# Soccer_V4.net
KiCad netlist of a schematic drawn in EAGLE
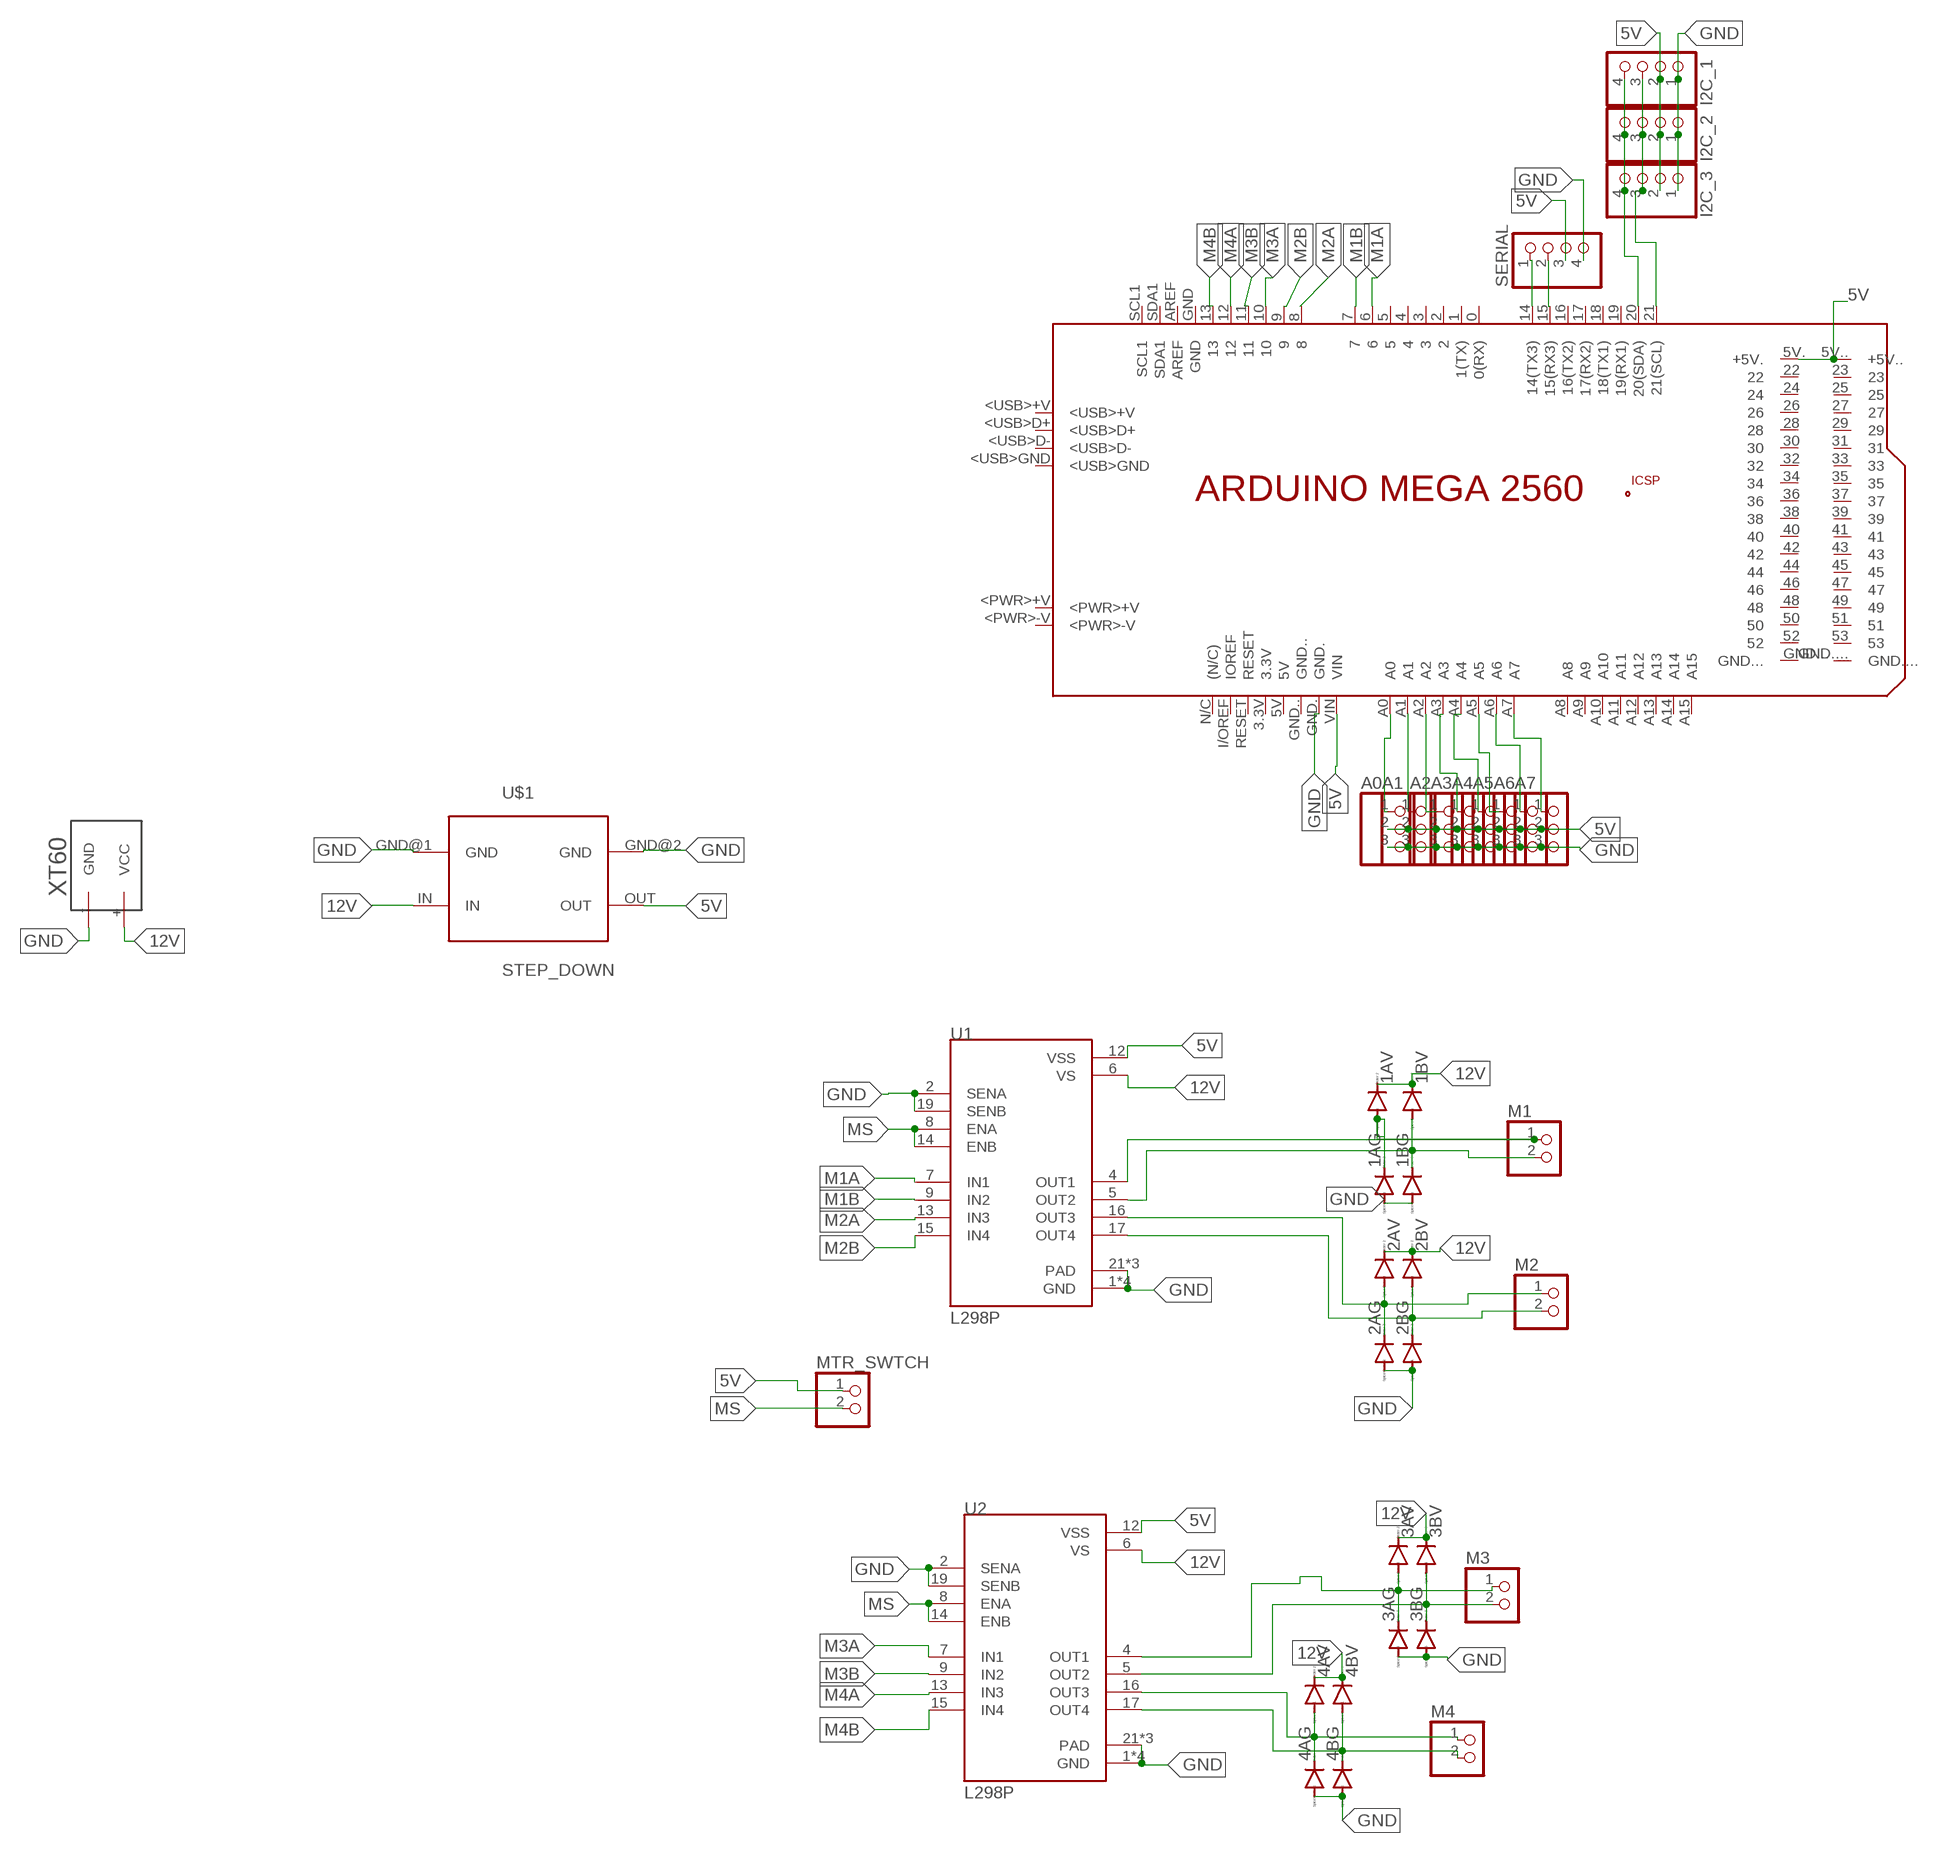
[diagram p0: schematic, sheet 1]

(export (version "E")
  (design (tool "Eeschema 10.0.6"))
  (components
    (comp (ref "1AG")
      (value "1N4004")
      (footprint "eagle-import:DO41-10")
      (libsource (lib "eagle-import") (part "1N4004"))
    )
    (comp (ref "1AV")
      (value "1N4004")
      (footprint "eagle-import:DO41-10")
      (libsource (lib "eagle-import") (part "1N4004"))
    )
    (comp (ref "1BG")
      (value "1N4004")
      (footprint "eagle-import:DO41-10")
      (libsource (lib "eagle-import") (part "1N4004"))
    )
    (comp (ref "1BV")
      (value "1N4004")
      (footprint "eagle-import:DO41-10")
      (libsource (lib "eagle-import") (part "1N4004"))
    )
    (comp (ref "2AG")
      (value "1N4004")
      (footprint "eagle-import:DO41-10")
      (libsource (lib "eagle-import") (part "1N4004"))
    )
    (comp (ref "2AV")
      (value "1N4004")
      (footprint "eagle-import:DO41-10")
      (libsource (lib "eagle-import") (part "1N4004"))
    )
    (comp (ref "2BG")
      (value "1N4004")
      (footprint "eagle-import:DO41-10")
      (libsource (lib "eagle-import") (part "1N4004"))
    )
    (comp (ref "2BV")
      (value "1N4004")
      (footprint "eagle-import:DO41-10")
      (libsource (lib "eagle-import") (part "1N4004"))
    )
    (comp (ref "3AG")
      (value "1N4004")
      (footprint "eagle-import:DO41-10")
      (libsource (lib "eagle-import") (part "1N4004"))
    )
    (comp (ref "3AV")
      (value "1N4004")
      (footprint "eagle-import:DO41-10")
      (libsource (lib "eagle-import") (part "1N4004"))
    )
    (comp (ref "3BG")
      (value "1N4004")
      (footprint "eagle-import:DO41-10")
      (libsource (lib "eagle-import") (part "1N4004"))
    )
    (comp (ref "3BV")
      (value "1N4004")
      (footprint "eagle-import:DO41-10")
      (libsource (lib "eagle-import") (part "1N4004"))
    )
    (comp (ref "4AG")
      (value "1N4004")
      (footprint "eagle-import:DO41-10")
      (libsource (lib "eagle-import") (part "1N4004"))
    )
    (comp (ref "4AV")
      (value "1N4004")
      (footprint "eagle-import:DO41-10")
      (libsource (lib "eagle-import") (part "1N4004"))
    )
    (comp (ref "4BG")
      (value "1N4004")
      (footprint "eagle-import:DO41-10")
      (libsource (lib "eagle-import") (part "1N4004"))
    )
    (comp (ref "4BV")
      (value "1N4004")
      (footprint "eagle-import:DO41-10")
      (libsource (lib "eagle-import") (part "1N4004"))
    )
    (comp (ref "A0")
      (value "PINHD-1X3")
      (footprint "eagle-import:1X03")
      (libsource (lib "eagle-import") (part "PINHD-1X3"))
    )
    (comp (ref "A1")
      (value "PINHD-1X3")
      (footprint "eagle-import:1X03")
      (libsource (lib "eagle-import") (part "PINHD-1X3"))
    )
    (comp (ref "A2")
      (value "PINHD-1X3")
      (footprint "eagle-import:1X03")
      (libsource (lib "eagle-import") (part "PINHD-1X3"))
    )
    (comp (ref "A3")
      (value "PINHD-1X3")
      (footprint "eagle-import:1X03")
      (libsource (lib "eagle-import") (part "PINHD-1X3"))
    )
    (comp (ref "A4")
      (value "PINHD-1X3")
      (footprint "eagle-import:1X03")
      (libsource (lib "eagle-import") (part "PINHD-1X3"))
    )
    (comp (ref "A5")
      (value "PINHD-1X3")
      (footprint "eagle-import:1X03")
      (libsource (lib "eagle-import") (part "PINHD-1X3"))
    )
    (comp (ref "A6")
      (value "PINHD-1X3")
      (footprint "eagle-import:1X03")
      (libsource (lib "eagle-import") (part "PINHD-1X3"))
    )
    (comp (ref "A7")
      (value "PINHD-1X3")
      (footprint "eagle-import:1X03")
      (libsource (lib "eagle-import") (part "PINHD-1X3"))
    )
    (comp (ref "I2C_1")
      (value "PINHD-1X4")
      (footprint "eagle-import:1X04")
      (libsource (lib "eagle-import") (part "PINHD-1X4"))
    )
    (comp (ref "I2C_2")
      (value "PINHD-1X4")
      (footprint "eagle-import:1X04")
      (libsource (lib "eagle-import") (part "PINHD-1X4"))
    )
    (comp (ref "I2C_3")
      (value "PINHD-1X4")
      (footprint "eagle-import:1X04")
      (libsource (lib "eagle-import") (part "PINHD-1X4"))
    )
    (comp (ref "M1")
      (value "PINHD-1X2")
      (footprint "eagle-import:1X02")
      (libsource (lib "eagle-import") (part "PINHD-1X2"))
    )
    (comp (ref "M2")
      (value "PINHD-1X2")
      (footprint "eagle-import:1X02")
      (libsource (lib "eagle-import") (part "PINHD-1X2"))
    )
    (comp (ref "M3")
      (value "PINHD-1X2")
      (footprint "eagle-import:1X02")
      (libsource (lib "eagle-import") (part "PINHD-1X2"))
    )
    (comp (ref "M4")
      (value "PINHD-1X2")
      (footprint "eagle-import:1X02")
      (libsource (lib "eagle-import") (part "PINHD-1X2"))
    )
    (comp (ref "MTR_SWTCH")
      (value "PINHD-1X2")
      (footprint "eagle-import:1X02")
      (libsource (lib "eagle-import") (part "PINHD-1X2"))
    )
    (comp (ref "PCB1")
      (value "ARDUINO_MEGA2560")
      (footprint "eagle-import:ARDUINO_MEGA2560")
      (libsource (lib "eagle-import") (part "ARDUINO_MEGA2560"))
    )
    (comp (ref "SERIAL")
      (value "PINHD-1X4")
      (footprint "eagle-import:1X04")
      (libsource (lib "eagle-import") (part "PINHD-1X4"))
    )
    (comp (ref "U$1")
      (value "STEP_DOWN")
      (footprint "eagle-import:STEP_DOWN_5V")
      (libsource (lib "eagle-import") (part "STEP_DOWN"))
    )
    (comp (ref "U$2")
      (value "XT60")
      (footprint "eagle-import:XT60")
      (libsource (lib "eagle-import") (part "XT60"))
    )
    (comp (ref "U1")
      (value "L298P")
      (footprint "eagle-import:SOIC127P1420X360-20N")
      (fields (field (name "MF") "STMicroelectronics"))
      (libsource (lib "eagle-import") (part "L298P"))
    )
    (comp (ref "U2")
      (value "L298P")
      (footprint "eagle-import:SOIC127P1420X360-20N")
      (fields (field (name "MF") "STMicroelectronics"))
      (libsource (lib "eagle-import") (part "L298P"))
    )
  )
  (nets
    (net (code "1") (name "5V") (class "Default")
      (node (ref "A0") (pin "2") (pinfunction "2_2") (pintype "passive"))
      (node (ref "A1") (pin "2") (pinfunction "2_2") (pintype "passive"))
      (node (ref "A2") (pin "2") (pinfunction "2_2") (pintype "passive"))
      (node (ref "A3") (pin "2") (pinfunction "2_2") (pintype "passive"))
      (node (ref "A4") (pin "2") (pinfunction "2_2") (pintype "passive"))
      (node (ref "A5") (pin "2") (pinfunction "2_2") (pintype "passive"))
      (node (ref "A6") (pin "2") (pinfunction "2_2") (pintype "passive"))
      (node (ref "A7") (pin "2") (pinfunction "2_2") (pintype "passive"))
      (node (ref "I2C_1") (pin "2") (pinfunction "2_2") (pintype "passive"))
      (node (ref "I2C_2") (pin "2") (pinfunction "2_2") (pintype "passive"))
      (node (ref "I2C_3") (pin "2") (pinfunction "2_2") (pintype "passive"))
      (node (ref "MTR_SWTCH") (pin "1") (pinfunction "1_1") (pintype "passive"))
      (node (ref "PCB1") (pin "5V.") (pinfunction "+5V._5V.") (pintype "bidirectional"))
      (node (ref "PCB1") (pin "5V..") (pinfunction "+5V.._5V..") (pintype "bidirectional"))
      (node (ref "PCB1") (pin "VIN") (pinfunction "VIN_VIN") (pintype "bidirectional"))
      (node (ref "SERIAL") (pin "3") (pinfunction "3_3") (pintype "passive"))
      (node (ref "U$1") (pin "OUT") (pinfunction "OUT_OUT") (pintype "bidirectional"))
      (node (ref "U1") (pin "12") (pinfunction "VSS_12") (pintype "power_in"))
      (node (ref "U2") (pin "12") (pinfunction "VSS_12") (pintype "power_in"))
    )
    (net (code "2") (name "12V") (class "Default")
      (node (ref "1AV") (pin "C") (pinfunction "C_C") (pintype "passive"))
      (node (ref "1BV") (pin "C") (pinfunction "C_C") (pintype "passive"))
      (node (ref "2AV") (pin "C") (pinfunction "C_C") (pintype "passive"))
      (node (ref "2BV") (pin "C") (pinfunction "C_C") (pintype "passive"))
      (node (ref "3AV") (pin "C") (pinfunction "C_C") (pintype "passive"))
      (node (ref "3BV") (pin "C") (pinfunction "C_C") (pintype "passive"))
      (node (ref "4AV") (pin "C") (pinfunction "C_C") (pintype "passive"))
      (node (ref "4BV") (pin "C") (pinfunction "C_C") (pintype "passive"))
      (node (ref "U$1") (pin "IN") (pinfunction "IN_IN") (pintype "bidirectional"))
      (node (ref "U$2") (pin "+") (pinfunction "VCC_+") (pintype "bidirectional"))
      (node (ref "U1") (pin "6") (pinfunction "VS_6") (pintype "power_in"))
      (node (ref "U2") (pin "6") (pinfunction "VS_6") (pintype "power_in"))
    )
    (net (code "3") (name "GND") (class "Default")
      (node (ref "1AG") (pin "A") (pinfunction "A_A") (pintype "passive"))
      (node (ref "1BG") (pin "A") (pinfunction "A_A") (pintype "passive"))
      (node (ref "2AG") (pin "A") (pinfunction "A_A") (pintype "passive"))
      (node (ref "2BG") (pin "A") (pinfunction "A_A") (pintype "passive"))
      (node (ref "3AG") (pin "A") (pinfunction "A_A") (pintype "passive"))
      (node (ref "3BG") (pin "A") (pinfunction "A_A") (pintype "passive"))
      (node (ref "4AG") (pin "A") (pinfunction "A_A") (pintype "passive"))
      (node (ref "4BG") (pin "A") (pinfunction "A_A") (pintype "passive"))
      (node (ref "A0") (pin "3") (pinfunction "3_3") (pintype "passive"))
      (node (ref "A1") (pin "3") (pinfunction "3_3") (pintype "passive"))
      (node (ref "A2") (pin "3") (pinfunction "3_3") (pintype "passive"))
      (node (ref "A3") (pin "3") (pinfunction "3_3") (pintype "passive"))
      (node (ref "A4") (pin "3") (pinfunction "3_3") (pintype "passive"))
      (node (ref "A5") (pin "3") (pinfunction "3_3") (pintype "passive"))
      (node (ref "A6") (pin "3") (pinfunction "3_3") (pintype "passive"))
      (node (ref "A7") (pin "3") (pinfunction "3_3") (pintype "passive"))
      (node (ref "I2C_1") (pin "1") (pinfunction "1_1") (pintype "passive"))
      (node (ref "I2C_2") (pin "1") (pinfunction "1_1") (pintype "passive"))
      (node (ref "I2C_3") (pin "1") (pinfunction "1_1") (pintype "passive"))
      (node (ref "PCB1") (pin "GND.") (pinfunction "GND._GND.") (pintype "bidirectional"))
      (node (ref "SERIAL") (pin "4") (pinfunction "4_4") (pintype "passive"))
      (node (ref "U$1") (pin "GND@1") (pinfunction "GND_GND@1") (pintype "bidirectional"))
      (node (ref "U$1") (pin "GND@2") (pinfunction "GND_GND@2") (pintype "bidirectional"))
      (node (ref "U$2") (pin "-") (pinfunction "GND_-") (pintype "bidirectional"))
      (node (ref "U1") (pin "1") (pinfunction "GND_1") (pintype "passive"))
      (node (ref "U1") (pin "10") (pinfunction "GND_10") (pintype "passive"))
      (node (ref "U1") (pin "11") (pinfunction "GND_11") (pintype "passive"))
      (node (ref "U1") (pin "19") (pinfunction "SENB_19") (pintype "input"))
      (node (ref "U1") (pin "2") (pinfunction "SENA_2") (pintype "input"))
      (node (ref "U1") (pin "20") (pinfunction "GND_20") (pintype "passive"))
      (node (ref "U1") (pin "21") (pinfunction "PAD_21") (pintype "passive"))
      (node (ref "U1") (pin "22") (pinfunction "PAD_22") (pintype "passive"))
      (node (ref "U1") (pin "23") (pinfunction "PAD_23") (pintype "passive"))
      (node (ref "U2") (pin "1") (pinfunction "GND_1") (pintype "passive"))
      (node (ref "U2") (pin "10") (pinfunction "GND_10") (pintype "passive"))
      (node (ref "U2") (pin "11") (pinfunction "GND_11") (pintype "passive"))
      (node (ref "U2") (pin "19") (pinfunction "SENB_19") (pintype "input"))
      (node (ref "U2") (pin "2") (pinfunction "SENA_2") (pintype "input"))
      (node (ref "U2") (pin "20") (pinfunction "GND_20") (pintype "passive"))
      (node (ref "U2") (pin "21") (pinfunction "PAD_21") (pintype "passive"))
      (node (ref "U2") (pin "22") (pinfunction "PAD_22") (pintype "passive"))
      (node (ref "U2") (pin "23") (pinfunction "PAD_23") (pintype "passive"))
    )
    (net (code "4") (name "M1A") (class "Default")
      (node (ref "PCB1") (pin "6") (pinfunction "6_6") (pintype "bidirectional"))
      (node (ref "U1") (pin "7") (pinfunction "IN1_7") (pintype "input"))
    )
    (net (code "5") (name "M1B") (class "Default")
      (node (ref "PCB1") (pin "7") (pinfunction "7_7") (pintype "bidirectional"))
      (node (ref "U1") (pin "9") (pinfunction "IN2_9") (pintype "input"))
    )
    (net (code "6") (name "M2A") (class "Default")
      (node (ref "PCB1") (pin "8") (pinfunction "8_8") (pintype "bidirectional"))
      (node (ref "U1") (pin "13") (pinfunction "IN3_13") (pintype "input"))
    )
    (net (code "7") (name "M2B") (class "Default")
      (node (ref "PCB1") (pin "9") (pinfunction "9_9") (pintype "bidirectional"))
      (node (ref "U1") (pin "15") (pinfunction "IN4_15") (pintype "input"))
    )
    (net (code "8") (name "M3A") (class "Default")
      (node (ref "PCB1") (pin "10") (pinfunction "10_10") (pintype "bidirectional"))
      (node (ref "U2") (pin "7") (pinfunction "IN1_7") (pintype "input"))
    )
    (net (code "9") (name "M3B") (class "Default")
      (node (ref "PCB1") (pin "11") (pinfunction "11_11") (pintype "bidirectional"))
      (node (ref "U2") (pin "9") (pinfunction "IN2_9") (pintype "input"))
    )
    (net (code "10") (name "M4A") (class "Default")
      (node (ref "PCB1") (pin "12") (pinfunction "12_12") (pintype "bidirectional"))
      (node (ref "U2") (pin "13") (pinfunction "IN3_13") (pintype "input"))
    )
    (net (code "11") (name "M4B") (class "Default")
      (node (ref "PCB1") (pin "13") (pinfunction "13_13") (pintype "bidirectional"))
      (node (ref "U2") (pin "15") (pinfunction "IN4_15") (pintype "input"))
    )
    (net (code "12") (name "MS") (class "Default")
      (node (ref "MTR_SWTCH") (pin "2") (pinfunction "2_2") (pintype "passive"))
      (node (ref "U1") (pin "14") (pinfunction "ENB_14") (pintype "input"))
      (node (ref "U1") (pin "8") (pinfunction "ENA_8") (pintype "input"))
      (node (ref "U2") (pin "14") (pinfunction "ENB_14") (pintype "input"))
      (node (ref "U2") (pin "8") (pinfunction "ENA_8") (pintype "input"))
    )
    (net (code "13") (name "Net-(A0-Pad1)") (class "Default")
      (node (ref "A0") (pin "1") (pinfunction "1_1") (pintype "passive"))
      (node (ref "PCB1") (pin "A0") (pinfunction "A0_A0") (pintype "bidirectional"))
    )
    (net (code "14") (name "Net-(A1-Pad1)") (class "Default")
      (node (ref "A1") (pin "1") (pinfunction "1_1") (pintype "passive"))
      (node (ref "PCB1") (pin "A1") (pinfunction "A1_A1") (pintype "bidirectional"))
    )
    (net (code "15") (name "Net-(A2-Pad1)") (class "Default")
      (node (ref "A2") (pin "1") (pinfunction "1_1") (pintype "passive"))
      (node (ref "PCB1") (pin "A2") (pinfunction "A2_A2") (pintype "bidirectional"))
    )
    (net (code "16") (name "Net-(A3-Pad1)") (class "Default")
      (node (ref "A3") (pin "1") (pinfunction "1_1") (pintype "passive"))
      (node (ref "PCB1") (pin "A3") (pinfunction "A3_A3") (pintype "bidirectional"))
    )
    (net (code "17") (name "Net-(A4-Pad1)") (class "Default")
      (node (ref "A4") (pin "1") (pinfunction "1_1") (pintype "passive"))
      (node (ref "PCB1") (pin "A4") (pinfunction "A4_A4") (pintype "bidirectional"))
    )
    (net (code "18") (name "Net-(A5-Pad1)") (class "Default")
      (node (ref "A5") (pin "1") (pinfunction "1_1") (pintype "passive"))
      (node (ref "PCB1") (pin "A5") (pinfunction "A5_A5") (pintype "bidirectional"))
    )
    (net (code "19") (name "Net-(A6-Pad1)") (class "Default")
      (node (ref "A6") (pin "1") (pinfunction "1_1") (pintype "passive"))
      (node (ref "PCB1") (pin "A6") (pinfunction "A6_A6") (pintype "bidirectional"))
    )
    (net (code "20") (name "Net-(A7-Pad1)") (class "Default")
      (node (ref "A7") (pin "1") (pinfunction "1_1") (pintype "passive"))
      (node (ref "PCB1") (pin "A7") (pinfunction "A7_A7") (pintype "bidirectional"))
    )
    (net (code "21") (name "Net-(PCB1-14(TX3))") (class "Default")
      (node (ref "PCB1") (pin "14") (pinfunction "14(TX3)_14") (pintype "bidirectional"))
      (node (ref "SERIAL") (pin "1") (pinfunction "1_1") (pintype "passive"))
    )
    (net (code "22") (name "Net-(PCB1-15(RX3))") (class "Default")
      (node (ref "PCB1") (pin "15") (pinfunction "15(RX3)_15") (pintype "bidirectional"))
      (node (ref "SERIAL") (pin "2") (pinfunction "2_2") (pintype "passive"))
    )
    (net (code "23") (name "Net-(PCB1-20(SDA))") (class "Default")
      (node (ref "I2C_1") (pin "4") (pinfunction "4_4") (pintype "passive"))
      (node (ref "I2C_2") (pin "4") (pinfunction "4_4") (pintype "passive"))
      (node (ref "I2C_3") (pin "4") (pinfunction "4_4") (pintype "passive"))
      (node (ref "PCB1") (pin "20") (pinfunction "20(SDA)_20") (pintype "bidirectional"))
    )
    (net (code "24") (name "Net-(PCB1-21(SCL))") (class "Default")
      (node (ref "I2C_1") (pin "3") (pinfunction "3_3") (pintype "passive"))
      (node (ref "I2C_2") (pin "3") (pinfunction "3_3") (pintype "passive"))
      (node (ref "I2C_3") (pin "3") (pinfunction "3_3") (pintype "passive"))
      (node (ref "PCB1") (pin "21") (pinfunction "21(SCL)_21") (pintype "bidirectional"))
    )
    (net (code "25") (name "Net-(U1-OUT1)") (class "Default")
      (node (ref "1AG") (pin "C") (pinfunction "C_C") (pintype "passive"))
      (node (ref "1AV") (pin "A") (pinfunction "A_A") (pintype "passive"))
      (node (ref "M1") (pin "1") (pinfunction "1_1") (pintype "passive"))
      (node (ref "U1") (pin "4") (pinfunction "OUT1_4") (pintype "output"))
    )
    (net (code "26") (name "Net-(U1-OUT2)") (class "Default")
      (node (ref "1BG") (pin "C") (pinfunction "C_C") (pintype "passive"))
      (node (ref "1BV") (pin "A") (pinfunction "A_A") (pintype "passive"))
      (node (ref "M1") (pin "2") (pinfunction "2_2") (pintype "passive"))
      (node (ref "U1") (pin "5") (pinfunction "OUT2_5") (pintype "output"))
    )
    (net (code "27") (name "Net-(U1-OUT3)") (class "Default")
      (node (ref "2AG") (pin "C") (pinfunction "C_C") (pintype "passive"))
      (node (ref "2AV") (pin "A") (pinfunction "A_A") (pintype "passive"))
      (node (ref "M2") (pin "1") (pinfunction "1_1") (pintype "passive"))
      (node (ref "U1") (pin "16") (pinfunction "OUT3_16") (pintype "output"))
    )
    (net (code "28") (name "Net-(U1-OUT4)") (class "Default")
      (node (ref "2BG") (pin "C") (pinfunction "C_C") (pintype "passive"))
      (node (ref "2BV") (pin "A") (pinfunction "A_A") (pintype "passive"))
      (node (ref "M2") (pin "2") (pinfunction "2_2") (pintype "passive"))
      (node (ref "U1") (pin "17") (pinfunction "OUT4_17") (pintype "output"))
    )
    (net (code "29") (name "Net-(U2-OUT1)") (class "Default")
      (node (ref "3AG") (pin "C") (pinfunction "C_C") (pintype "passive"))
      (node (ref "3AV") (pin "A") (pinfunction "A_A") (pintype "passive"))
      (node (ref "M3") (pin "1") (pinfunction "1_1") (pintype "passive"))
      (node (ref "U2") (pin "4") (pinfunction "OUT1_4") (pintype "output"))
    )
    (net (code "30") (name "Net-(U2-OUT2)") (class "Default")
      (node (ref "3BG") (pin "C") (pinfunction "C_C") (pintype "passive"))
      (node (ref "3BV") (pin "A") (pinfunction "A_A") (pintype "passive"))
      (node (ref "M3") (pin "2") (pinfunction "2_2") (pintype "passive"))
      (node (ref "U2") (pin "5") (pinfunction "OUT2_5") (pintype "output"))
    )
    (net (code "31") (name "Net-(U2-OUT3)") (class "Default")
      (node (ref "4AG") (pin "C") (pinfunction "C_C") (pintype "passive"))
      (node (ref "4AV") (pin "A") (pinfunction "A_A") (pintype "passive"))
      (node (ref "M4") (pin "1") (pinfunction "1_1") (pintype "passive"))
      (node (ref "U2") (pin "16") (pinfunction "OUT3_16") (pintype "output"))
    )
    (net (code "32") (name "Net-(U2-OUT4)") (class "Default")
      (node (ref "4BG") (pin "C") (pinfunction "C_C") (pintype "passive"))
      (node (ref "4BV") (pin "A") (pinfunction "A_A") (pintype "passive"))
      (node (ref "M4") (pin "2") (pinfunction "2_2") (pintype "passive"))
      (node (ref "U2") (pin "17") (pinfunction "OUT4_17") (pintype "output"))
    )
    (net (code "33") (name "unconnected-(PCB1-(N{slash}C)-PadN{slash}C)") (class "Default")
      (node (ref "PCB1") (pin "N/C") (pinfunction "(N/C)_N/C") (pintype "bidirectional"))
    )
    (net (code "34") (name "unconnected-(PCB1-0(RX)-Pad0)") (class "Default")
      (node (ref "PCB1") (pin "0") (pinfunction "0(RX)_0") (pintype "bidirectional"))
    )
    (net (code "35") (name "unconnected-(PCB1-1(TX)-Pad1)") (class "Default")
      (node (ref "PCB1") (pin "1") (pinfunction "1(TX)_1") (pintype "bidirectional"))
    )
    (net (code "36") (name "unconnected-(PCB1-16(TX2)-Pad16)") (class "Default")
      (node (ref "PCB1") (pin "16") (pinfunction "16(TX2)_16") (pintype "bidirectional"))
    )
    (net (code "37") (name "unconnected-(PCB1-17(RX2)-Pad17)") (class "Default")
      (node (ref "PCB1") (pin "17") (pinfunction "17(RX2)_17") (pintype "bidirectional"))
    )
    (net (code "38") (name "unconnected-(PCB1-18(TX1)-Pad18)") (class "Default")
      (node (ref "PCB1") (pin "18") (pinfunction "18(TX1)_18") (pintype "bidirectional"))
    )
    (net (code "39") (name "unconnected-(PCB1-19(RX1)-Pad19)") (class "Default")
      (node (ref "PCB1") (pin "19") (pinfunction "19(RX1)_19") (pintype "bidirectional"))
    )
    (net (code "40") (name "unconnected-(PCB1-IOREF-PadI{slash}OREF)") (class "Default")
      (node (ref "PCB1") (pin "I/OREF") (pinfunction "IOREF_I/OREF") (pintype "bidirectional"))
    )
    (net (code "41") (name "unconnected-(PCB1-Pad+5V_)") (class "Default")
      (node (ref "PCB1") (pin "+5V_") (pinfunction "+5V__+5V_") (pintype "bidirectional"))
    )
    (net (code "42") (name "unconnected-(PCB1-Pad2)") (class "Default")
      (node (ref "PCB1") (pin "2") (pinfunction "2_2") (pintype "bidirectional"))
    )
    (net (code "43") (name "unconnected-(PCB1-Pad3)") (class "Default")
      (node (ref "PCB1") (pin "3") (pinfunction "3_3") (pintype "bidirectional"))
    )
    (net (code "44") (name "unconnected-(PCB1-Pad3.3V)") (class "Default")
      (node (ref "PCB1") (pin "3.3V") (pinfunction "3.3V_3.3V") (pintype "bidirectional"))
    )
    (net (code "45") (name "unconnected-(PCB1-Pad4)") (class "Default")
      (node (ref "PCB1") (pin "4") (pinfunction "4_4") (pintype "bidirectional"))
    )
    (net (code "46") (name "unconnected-(PCB1-Pad5)") (class "Default")
      (node (ref "PCB1") (pin "5") (pinfunction "5_5") (pintype "bidirectional"))
    )
    (net (code "47") (name "unconnected-(PCB1-Pad5V)") (class "Default")
      (node (ref "PCB1") (pin "5V") (pinfunction "5V_5V") (pintype "bidirectional"))
    )
    (net (code "48") (name "unconnected-(PCB1-Pad22)") (class "Default")
      (node (ref "PCB1") (pin "22") (pinfunction "22_22") (pintype "bidirectional"))
    )
    (net (code "49") (name "unconnected-(PCB1-Pad23)") (class "Default")
      (node (ref "PCB1") (pin "23") (pinfunction "23_23") (pintype "bidirectional"))
    )
    (net (code "50") (name "unconnected-(PCB1-Pad24)") (class "Default")
      (node (ref "PCB1") (pin "24") (pinfunction "24_24") (pintype "bidirectional"))
    )
    (net (code "51") (name "unconnected-(PCB1-Pad25)") (class "Default")
      (node (ref "PCB1") (pin "25") (pinfunction "25_25") (pintype "bidirectional"))
    )
    (net (code "52") (name "unconnected-(PCB1-Pad26)") (class "Default")
      (node (ref "PCB1") (pin "26") (pinfunction "26_26") (pintype "bidirectional"))
    )
    (net (code "53") (name "unconnected-(PCB1-Pad27)") (class "Default")
      (node (ref "PCB1") (pin "27") (pinfunction "27_27") (pintype "bidirectional"))
    )
    (net (code "54") (name "unconnected-(PCB1-Pad28)") (class "Default")
      (node (ref "PCB1") (pin "28") (pinfunction "28_28") (pintype "bidirectional"))
    )
    (net (code "55") (name "unconnected-(PCB1-Pad29)") (class "Default")
      (node (ref "PCB1") (pin "29") (pinfunction "29_29") (pintype "bidirectional"))
    )
    (net (code "56") (name "unconnected-(PCB1-Pad30)") (class "Default")
      (node (ref "PCB1") (pin "30") (pinfunction "30_30") (pintype "bidirectional"))
    )
    (net (code "57") (name "unconnected-(PCB1-Pad31)") (class "Default")
      (node (ref "PCB1") (pin "31") (pinfunction "31_31") (pintype "bidirectional"))
    )
    (net (code "58") (name "unconnected-(PCB1-Pad32)") (class "Default")
      (node (ref "PCB1") (pin "32") (pinfunction "32_32") (pintype "bidirectional"))
    )
    (net (code "59") (name "unconnected-(PCB1-Pad33)") (class "Default")
      (node (ref "PCB1") (pin "33") (pinfunction "33_33") (pintype "bidirectional"))
    )
    (net (code "60") (name "unconnected-(PCB1-Pad34)") (class "Default")
      (node (ref "PCB1") (pin "34") (pinfunction "34_34") (pintype "bidirectional"))
    )
    (net (code "61") (name "unconnected-(PCB1-Pad35)") (class "Default")
      (node (ref "PCB1") (pin "35") (pinfunction "35_35") (pintype "bidirectional"))
    )
    (net (code "62") (name "unconnected-(PCB1-Pad36)") (class "Default")
      (node (ref "PCB1") (pin "36") (pinfunction "36_36") (pintype "bidirectional"))
    )
    (net (code "63") (name "unconnected-(PCB1-Pad37)") (class "Default")
      (node (ref "PCB1") (pin "37") (pinfunction "37_37") (pintype "bidirectional"))
    )
    (net (code "64") (name "unconnected-(PCB1-Pad38)") (class "Default")
      (node (ref "PCB1") (pin "38") (pinfunction "38_38") (pintype "bidirectional"))
    )
    (net (code "65") (name "unconnected-(PCB1-Pad39)") (class "Default")
      (node (ref "PCB1") (pin "39") (pinfunction "39_39") (pintype "bidirectional"))
    )
    (net (code "66") (name "unconnected-(PCB1-Pad40)") (class "Default")
      (node (ref "PCB1") (pin "40") (pinfunction "40_40") (pintype "bidirectional"))
    )
    (net (code "67") (name "unconnected-(PCB1-Pad41)") (class "Default")
      (node (ref "PCB1") (pin "41") (pinfunction "41_41") (pintype "bidirectional"))
    )
    (net (code "68") (name "unconnected-(PCB1-Pad42)") (class "Default")
      (node (ref "PCB1") (pin "42") (pinfunction "42_42") (pintype "bidirectional"))
    )
    (net (code "69") (name "unconnected-(PCB1-Pad43)") (class "Default")
      (node (ref "PCB1") (pin "43") (pinfunction "43_43") (pintype "bidirectional"))
    )
    (net (code "70") (name "unconnected-(PCB1-Pad44)") (class "Default")
      (node (ref "PCB1") (pin "44") (pinfunction "44_44") (pintype "bidirectional"))
    )
    (net (code "71") (name "unconnected-(PCB1-Pad45)") (class "Default")
      (node (ref "PCB1") (pin "45") (pinfunction "45_45") (pintype "bidirectional"))
    )
    (net (code "72") (name "unconnected-(PCB1-Pad46)") (class "Default")
      (node (ref "PCB1") (pin "46") (pinfunction "46_46") (pintype "bidirectional"))
    )
    (net (code "73") (name "unconnected-(PCB1-Pad47)") (class "Default")
      (node (ref "PCB1") (pin "47") (pinfunction "47_47") (pintype "bidirectional"))
    )
    (net (code "74") (name "unconnected-(PCB1-Pad48)") (class "Default")
      (node (ref "PCB1") (pin "48") (pinfunction "48_48") (pintype "bidirectional"))
    )
    (net (code "75") (name "unconnected-(PCB1-Pad49)") (class "Default")
      (node (ref "PCB1") (pin "49") (pinfunction "49_49") (pintype "bidirectional"))
    )
    (net (code "76") (name "unconnected-(PCB1-Pad50)") (class "Default")
      (node (ref "PCB1") (pin "50") (pinfunction "50_50") (pintype "bidirectional"))
    )
    (net (code "77") (name "unconnected-(PCB1-Pad51)") (class "Default")
      (node (ref "PCB1") (pin "51") (pinfunction "51_51") (pintype "bidirectional"))
    )
    (net (code "78") (name "unconnected-(PCB1-Pad52)") (class "Default")
      (node (ref "PCB1") (pin "52") (pinfunction "52_52") (pintype "bidirectional"))
    )
    (net (code "79") (name "unconnected-(PCB1-Pad53)") (class "Default")
      (node (ref "PCB1") (pin "53") (pinfunction "53_53") (pintype "bidirectional"))
    )
    (net (code "80") (name "unconnected-(PCB1-Pad<PWR>+V)") (class "Default")
      (node (ref "PCB1") (pin "<PWR>+V") (pinfunction "<PWR>+V_<PWR>+V") (pintype "no_connect"))
    )
    (net (code "81") (name "unconnected-(PCB1-Pad<PWR>-V)") (class "Default")
      (node (ref "PCB1") (pin "<PWR>-V") (pinfunction "<PWR>-V_<PWR>-V") (pintype "no_connect"))
    )
    (net (code "82") (name "unconnected-(PCB1-Pad<USB>+V)") (class "Default")
      (node (ref "PCB1") (pin "<USB>+V") (pinfunction "<USB>+V_<USB>+V") (pintype "no_connect"))
    )
    (net (code "83") (name "unconnected-(PCB1-Pad<USB>D+)") (class "Default")
      (node (ref "PCB1") (pin "<USB>D+") (pinfunction "<USB>D+_<USB>D+") (pintype "no_connect"))
    )
    (net (code "84") (name "unconnected-(PCB1-Pad<USB>D-)") (class "Default")
      (node (ref "PCB1") (pin "<USB>D-") (pinfunction "<USB>D-_<USB>D-") (pintype "no_connect"))
    )
    (net (code "85") (name "unconnected-(PCB1-Pad<USB>GND)") (class "Default")
      (node (ref "PCB1") (pin "<USB>GND") (pinfunction "<USB>GND_<USB>GND") (pintype "no_connect"))
    )
    (net (code "86") (name "unconnected-(PCB1-PadA8)") (class "Default")
      (node (ref "PCB1") (pin "A8") (pinfunction "A8_A8") (pintype "bidirectional"))
    )
    (net (code "87") (name "unconnected-(PCB1-PadA9)") (class "Default")
      (node (ref "PCB1") (pin "A9") (pinfunction "A9_A9") (pintype "bidirectional"))
    )
    (net (code "88") (name "unconnected-(PCB1-PadA10)") (class "Default")
      (node (ref "PCB1") (pin "A10") (pinfunction "A10_A10") (pintype "bidirectional"))
    )
    (net (code "89") (name "unconnected-(PCB1-PadA11)") (class "Default")
      (node (ref "PCB1") (pin "A11") (pinfunction "A11_A11") (pintype "bidirectional"))
    )
    (net (code "90") (name "unconnected-(PCB1-PadA12)") (class "Default")
      (node (ref "PCB1") (pin "A12") (pinfunction "A12_A12") (pintype "bidirectional"))
    )
    (net (code "91") (name "unconnected-(PCB1-PadA13)") (class "Default")
      (node (ref "PCB1") (pin "A13") (pinfunction "A13_A13") (pintype "bidirectional"))
    )
    (net (code "92") (name "unconnected-(PCB1-PadA14)") (class "Default")
      (node (ref "PCB1") (pin "A14") (pinfunction "A14_A14") (pintype "bidirectional"))
    )
    (net (code "93") (name "unconnected-(PCB1-PadA15)") (class "Default")
      (node (ref "PCB1") (pin "A15") (pinfunction "A15_A15") (pintype "bidirectional"))
    )
    (net (code "94") (name "unconnected-(PCB1-PadAREF)") (class "Default")
      (node (ref "PCB1") (pin "AREF") (pinfunction "AREF_AREF") (pintype "bidirectional"))
    )
    (net (code "95") (name "unconnected-(PCB1-PadGND)") (class "Default")
      (node (ref "PCB1") (pin "GND") (pinfunction "GND_GND") (pintype "bidirectional"))
    )
    (net (code "96") (name "unconnected-(PCB1-PadGND..)") (class "Default")
      (node (ref "PCB1") (pin "GND..") (pinfunction "GND.._GND..") (pintype "bidirectional"))
    )
    (net (code "97") (name "unconnected-(PCB1-PadGND...)") (class "Default")
      (node (ref "PCB1") (pin "GND...") (pinfunction "GND..._GND...") (pintype "bidirectional"))
    )
    (net (code "98") (name "unconnected-(PCB1-PadGND....)") (class "Default")
      (node (ref "PCB1") (pin "GND....") (pinfunction "GND...._GND....") (pintype "bidirectional"))
    )
    (net (code "99") (name "unconnected-(PCB1-PadGND__)") (class "Default")
      (node (ref "PCB1") (pin "GND__") (pinfunction "GND___GND__") (pintype "bidirectional"))
    )
    (net (code "100") (name "unconnected-(PCB1-PadMISO)") (class "Default")
      (node (ref "PCB1") (pin "MISO") (pinfunction "MISO_MISO") (pintype "bidirectional"))
    )
    (net (code "101") (name "unconnected-(PCB1-PadMOSI)") (class "Default")
      (node (ref "PCB1") (pin "MOSI") (pinfunction "MOSI_MOSI") (pintype "bidirectional"))
    )
    (net (code "102") (name "unconnected-(PCB1-PadRESET)") (class "Default")
      (node (ref "PCB1") (pin "RESET") (pinfunction "RESET_RESET") (pintype "bidirectional"))
    )
    (net (code "103") (name "unconnected-(PCB1-PadRESET.)") (class "Default")
      (node (ref "PCB1") (pin "RESET.") (pinfunction "RESET._RESET.") (pintype "bidirectional"))
    )
    (net (code "104") (name "unconnected-(PCB1-PadSCK)") (class "Default")
      (node (ref "PCB1") (pin "SCK") (pinfunction "SCK_SCK") (pintype "bidirectional"))
    )
    (net (code "105") (name "unconnected-(PCB1-PadSCL1)") (class "Default")
      (node (ref "PCB1") (pin "SCL1") (pinfunction "SCL1_SCL1") (pintype "bidirectional"))
    )
    (net (code "106") (name "unconnected-(PCB1-PadSDA1)") (class "Default")
      (node (ref "PCB1") (pin "SDA1") (pinfunction "SDA1_SDA1") (pintype "bidirectional"))
    )
  )
)
